# LM2735.net
KiCad netlist of a schematic drawn in EAGLE
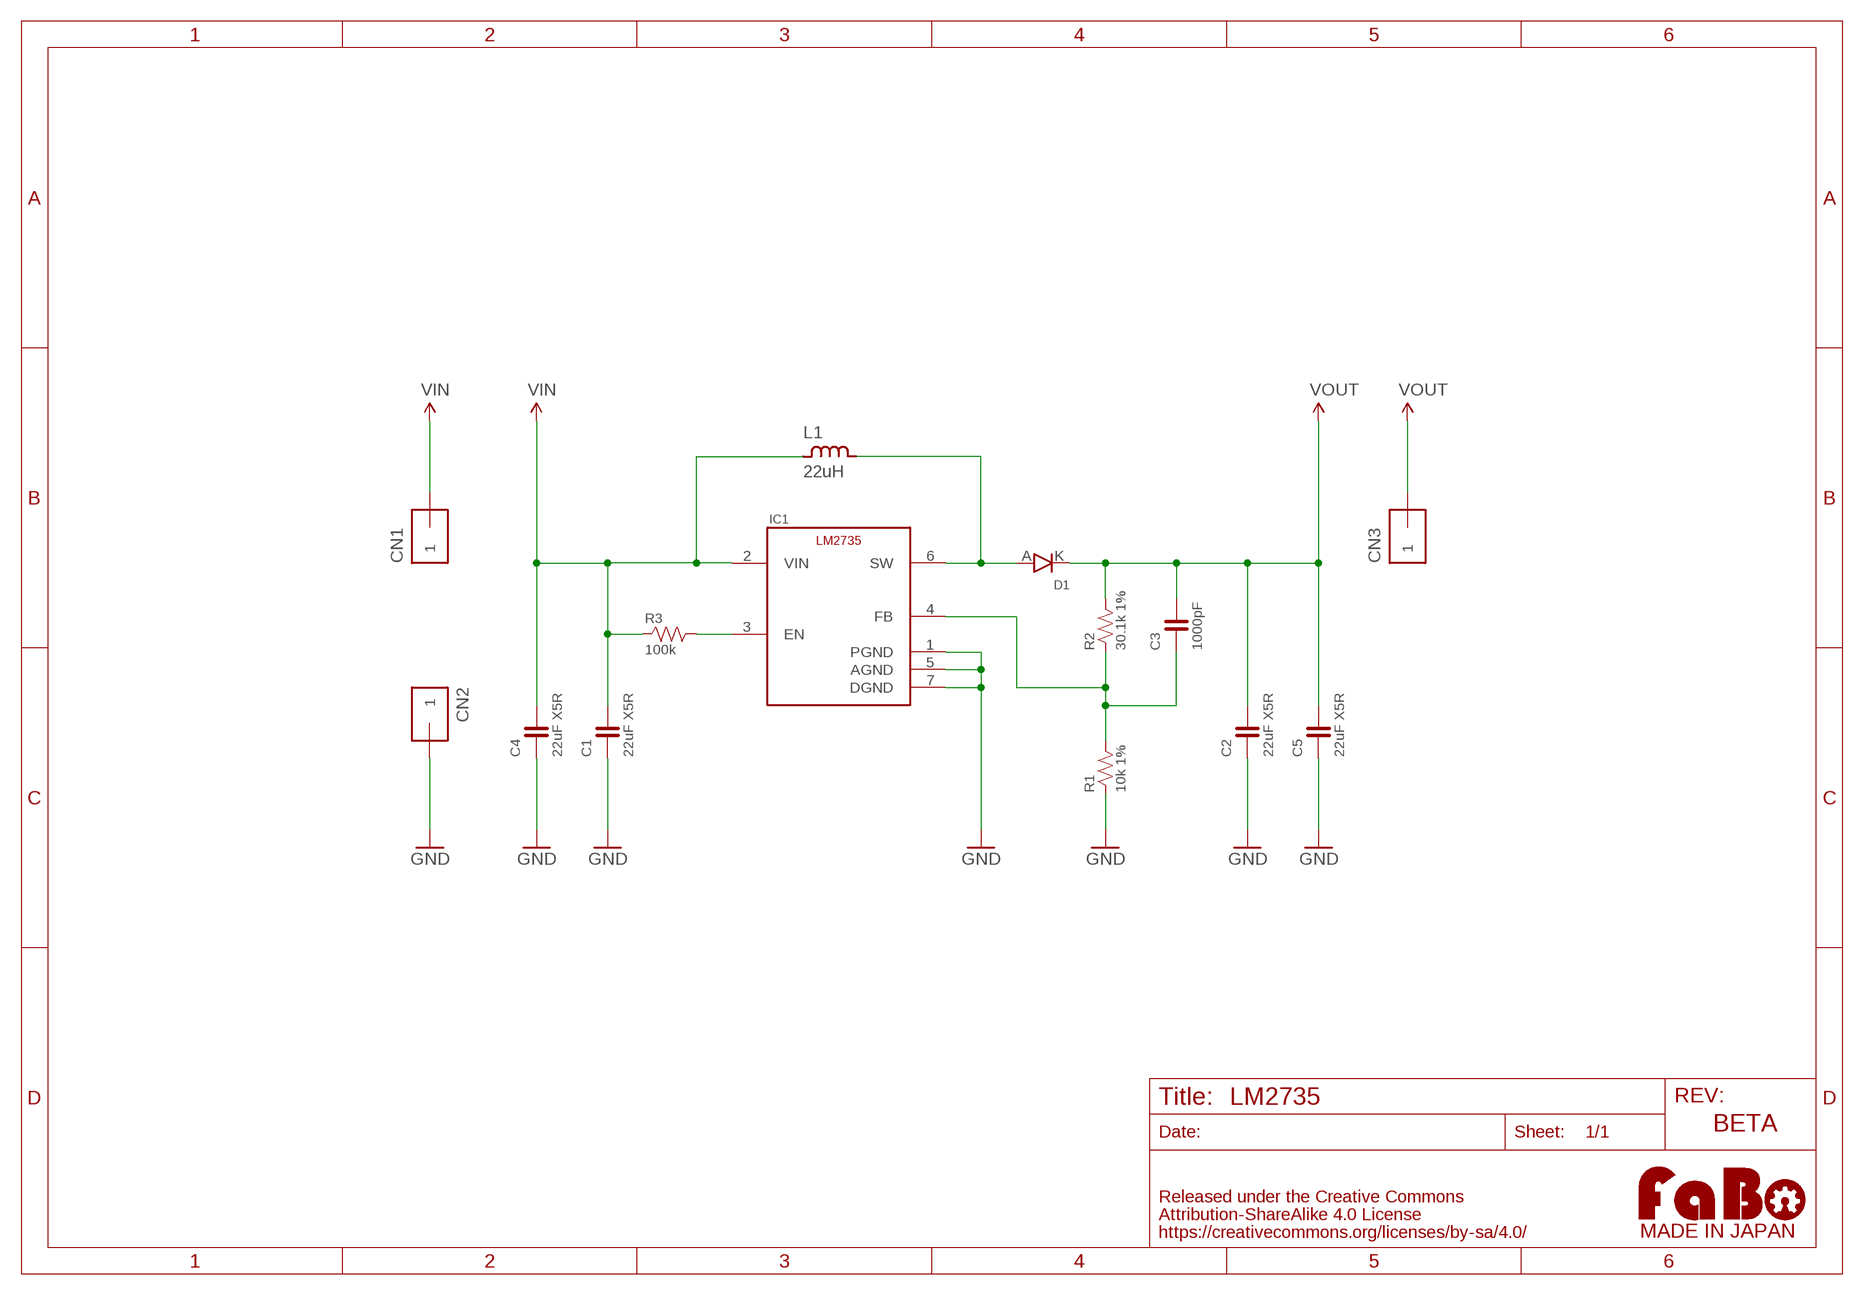
[diagram p0: schematic, sheet 1]

(export (version "E")
  (design (tool "Eeschema 10.0.6"))
  (components
    (comp (ref "C1")
      (value "22uF X5R")
      (footprint "eagle-import:0603-NARROW")
      (libsource (lib "eagle-import") (part "CAPACITOR-0603_NARROW"))
    )
    (comp (ref "C2")
      (value "22uF X5R")
      (footprint "eagle-import:0603-NARROW")
      (libsource (lib "eagle-import") (part "CAPACITOR-0603_NARROW"))
    )
    (comp (ref "C3")
      (value "1000pF")
      (footprint "eagle-import:0603-NARROW")
      (libsource (lib "eagle-import") (part "CAPACITOR-0603_NARROW"))
    )
    (comp (ref "C4")
      (value "22uF X5R")
      (footprint "eagle-import:0603-NARROW")
      (libsource (lib "eagle-import") (part "CAPACITOR-0603_NARROW"))
    )
    (comp (ref "C5")
      (value "22uF X5R")
      (footprint "eagle-import:0603-NARROW")
      (libsource (lib "eagle-import") (part "CAPACITOR-0603_NARROW"))
    )
    (comp (ref "CN1")
      (value "PIN_HEADER_1X1-SMALL")
      (footprint "eagle-import:PIN_1X1_SMALL")
      (libsource (lib "eagle-import") (part "PIN_HEADER_1X1-SMALL"))
    )
    (comp (ref "CN2")
      (value "PIN_HEADER_1X1-SMALL")
      (footprint "eagle-import:PIN_1X1_SMALL")
      (libsource (lib "eagle-import") (part "PIN_HEADER_1X1-SMALL"))
    )
    (comp (ref "CN3")
      (value "PIN_HEADER_1X1-SMALL")
      (footprint "eagle-import:PIN_1X1_SMALL")
      (libsource (lib "eagle-import") (part "PIN_HEADER_1X1-SMALL"))
    )
    (comp (ref "D1")
      (value "DIODE-STPS120M")
      (footprint "eagle-import:ST-MITE")
      (libsource (lib "eagle-import") (part "DIODE-STPS120M"))
    )
    (comp (ref "IC1")
      (value "LM2735YQSDX")
      (footprint "eagle-import:WSON-6")
      (libsource (lib "eagle-import") (part "LM2735YQSDX"))
    )
    (comp (ref "L1")
      (value "22uH")
      (footprint "eagle-import:NR5040")
      (libsource (lib "eagle-import") (part "INDUCTOR-NR5040"))
    )
    (comp (ref "R1")
      (value "10k 1%")
      (footprint "eagle-import:0603-NARROW")
      (libsource (lib "eagle-import") (part "RESISTOR-0603-NARROW"))
    )
    (comp (ref "R2")
      (value "30.1k 1%")
      (footprint "eagle-import:0603-NARROW")
      (libsource (lib "eagle-import") (part "RESISTOR-0603-NARROW"))
    )
    (comp (ref "R3")
      (value "100k")
      (footprint "eagle-import:0603-NARROW")
      (libsource (lib "eagle-import") (part "RESISTOR-0603-NARROW"))
    )
    (comp (ref "U$2")
      (value "LOGO_FABO-M_BOTTOM")
      (footprint "eagle-import:LOGO_FABO_MS_BOTTOM")
      (libsource (lib "eagle-import") (part "LOGO_FABO-M_BOTTOM"))
    )
  )
  (nets
    (net (code "1") (name "GND") (class "Default")
      (node (ref "C1") (pin "1") (pinfunction "1_1") (pintype "passive"))
      (node (ref "C2") (pin "1") (pinfunction "1_1") (pintype "passive"))
      (node (ref "C4") (pin "1") (pinfunction "1_1") (pintype "passive"))
      (node (ref "C5") (pin "1") (pinfunction "1_1") (pintype "passive"))
      (node (ref "CN2") (pin "1") (pinfunction "1_1") (pintype "bidirectional"))
      (node (ref "IC1") (pin "1") (pinfunction "PGND_1") (pintype "bidirectional"))
      (node (ref "IC1") (pin "5") (pinfunction "AGND_5") (pintype "bidirectional"))
      (node (ref "IC1") (pin "7") (pinfunction "DGND_7") (pintype "bidirectional"))
      (node (ref "R1") (pin "1") (pinfunction "1_1") (pintype "bidirectional"))
    )
    (net (code "2") (name "Net-(IC1-EN)") (class "Default")
      (node (ref "IC1") (pin "3") (pinfunction "EN_3") (pintype "bidirectional"))
      (node (ref "R3") (pin "2") (pinfunction "2_2") (pintype "bidirectional"))
    )
    (net (code "3") (name "Net-(IC1-FB)") (class "Default")
      (node (ref "C3") (pin "1") (pinfunction "1_1") (pintype "passive"))
      (node (ref "IC1") (pin "4") (pinfunction "FB_4") (pintype "bidirectional"))
      (node (ref "R1") (pin "2") (pinfunction "2_2") (pintype "bidirectional"))
      (node (ref "R2") (pin "1") (pinfunction "1_1") (pintype "bidirectional"))
    )
    (net (code "4") (name "Net-(IC1-SW)") (class "Default")
      (node (ref "D1") (pin "A") (pinfunction "A_A") (pintype "bidirectional"))
      (node (ref "IC1") (pin "6") (pinfunction "SW_6") (pintype "bidirectional"))
      (node (ref "L1") (pin "2") (pinfunction "2_2") (pintype "bidirectional"))
    )
    (net (code "5") (name "VIN") (class "Default")
      (node (ref "C1") (pin "2") (pinfunction "2_2") (pintype "passive"))
      (node (ref "C4") (pin "2") (pinfunction "2_2") (pintype "passive"))
      (node (ref "CN1") (pin "1") (pinfunction "1_1") (pintype "bidirectional"))
      (node (ref "IC1") (pin "2") (pinfunction "VIN_2") (pintype "bidirectional"))
      (node (ref "L1") (pin "1") (pinfunction "1_1") (pintype "bidirectional"))
      (node (ref "R3") (pin "1") (pinfunction "1_1") (pintype "bidirectional"))
    )
    (net (code "6") (name "VOUT") (class "Default")
      (node (ref "C2") (pin "2") (pinfunction "2_2") (pintype "passive"))
      (node (ref "C3") (pin "2") (pinfunction "2_2") (pintype "passive"))
      (node (ref "C5") (pin "2") (pinfunction "2_2") (pintype "passive"))
      (node (ref "CN3") (pin "1") (pinfunction "1_1") (pintype "bidirectional"))
      (node (ref "D1") (pin "K") (pinfunction "K_K") (pintype "bidirectional"))
      (node (ref "R2") (pin "2") (pinfunction "2_2") (pintype "bidirectional"))
    )
  )
)
